# MotorDriver.net
KiCad netlist of a schematic drawn in Altium Designer
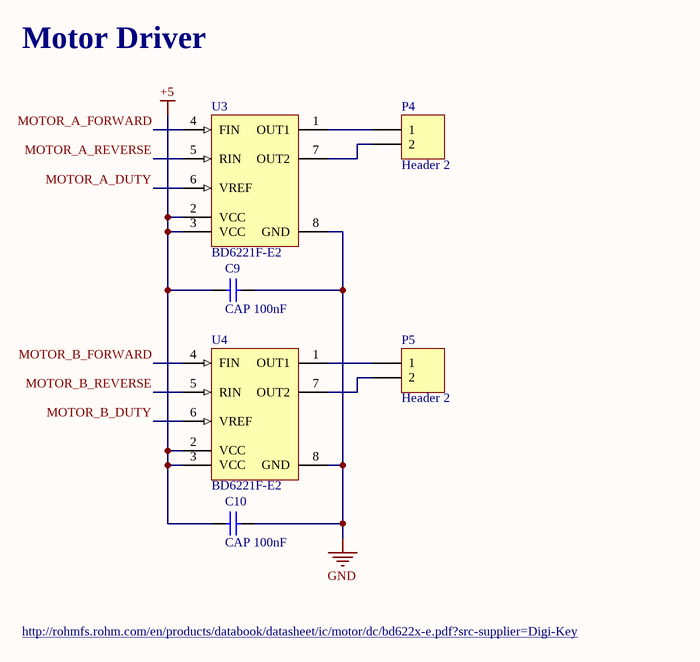
[diagram p0: MotorDriver.SchDoc]

(export (version "E")
  (design (tool "Eeschema 10.0.6"))
  (components
    (comp (ref "C9")
      (value "CAP 100nF")
      (footprint "CAPC0603(1608)100_M")
      (description "CAP 100nF 16V ±5% 0603 (1608 Metric) Thickness 1mm SMD")
      (fields (field (name "TOLERANCE") "Â±5%"))
      (libsource (lib "Altium Content Vault") (part "CAP"))
    )
    (comp (ref "C10")
      (value "CAP 100nF")
      (footprint "CAPC0603(1608)100_M")
      (description "CAP 100nF 16V ±5% 0603 (1608 Metric) Thickness 1mm SMD")
      (fields (field (name "TOLERANCE") "Â±5%"))
      (libsource (lib "Altium Content Vault") (part "CAP"))
    )
    (comp (ref "P4")
      (value "Header 2")
      (footprint "HDR1X2")
      (description "Header, 2-Pin")
      (fields (field (name "PUBLISHER") "Altium Limited"))
      (libsource (lib "Miscellaneous Connectors") (part "Header 2"))
    )
    (comp (ref "P5")
      (value "Header 2")
      (footprint "HDR1X2")
      (description "Header, 2-Pin")
      (fields (field (name "PUBLISHER") "Altium Limited"))
      (libsource (lib "Miscellaneous Connectors") (part "Header 2"))
    )
    (comp (ref "U3")
      (value "BD6221F-E2")
      (footprint "ROHM-SOP-8_V")
      (description "DC Brush Motor Driver, 6 to 18 V, 1 A, -40 to 85 degC, 8-Pin SOP, RoHS, Tape and Reel")
      (fields (field (name "MANUFACTURER") "ROHM Semiconductor"))
      (libsource (lib "Altium Content Vault") (part "ROHM-BD6221F-SOP-8"))
    )
    (comp (ref "U4")
      (value "BD6221F-E2")
      (footprint "ROHM-SOP-8_V")
      (description "DC Brush Motor Driver, 6 to 18 V, 1 A, -40 to 85 degC, 8-Pin SOP, RoHS, Tape and Reel")
      (fields (field (name "MANUFACTURER") "ROHM Semiconductor"))
      (libsource (lib "Altium Content Vault") (part "ROHM-BD6221F-SOP-8"))
    )
  )
  (nets
    (net (code "1") (name "+5") (class "Default")
      (node (ref "C10") (pin "2") (pinfunction "2_2") (pintype "passive"))
      (node (ref "C9") (pin "2") (pinfunction "2_2") (pintype "passive"))
      (node (ref "U3") (pin "2") (pinfunction "VCC_2") (pintype "power_in"))
      (node (ref "U3") (pin "3") (pinfunction "VCC_3") (pintype "power_in"))
      (node (ref "U4") (pin "2") (pinfunction "VCC_2") (pintype "power_in"))
      (node (ref "U4") (pin "3") (pinfunction "VCC_3") (pintype "power_in"))
    )
    (net (code "2") (name "/MOTOR_A_DUTY") (class "Default")
      (node (ref "U3") (pin "6") (pinfunction "VREF_6") (pintype "input"))
    )
    (net (code "3") (name "/MOTOR_A_FORWARD") (class "Default")
      (node (ref "U3") (pin "4") (pinfunction "FIN_4") (pintype "input"))
    )
    (net (code "4") (name "/MOTOR_A_REVERSE") (class "Default")
      (node (ref "U3") (pin "5") (pinfunction "RIN_5") (pintype "input"))
    )
    (net (code "5") (name "/MOTOR_B_DUTY") (class "Default")
      (node (ref "U4") (pin "6") (pinfunction "VREF_6") (pintype "input"))
    )
    (net (code "6") (name "/MOTOR_B_FORWARD") (class "Default")
      (node (ref "U4") (pin "4") (pinfunction "FIN_4") (pintype "input"))
    )
    (net (code "7") (name "/MOTOR_B_REVERSE") (class "Default")
      (node (ref "U4") (pin "5") (pinfunction "RIN_5") (pintype "input"))
    )
    (net (code "8") (name "GND") (class "Default")
      (node (ref "C10") (pin "1") (pinfunction "1_1") (pintype "passive"))
      (node (ref "C9") (pin "1") (pinfunction "1_1") (pintype "passive"))
      (node (ref "U3") (pin "8") (pinfunction "GND_8") (pintype "power_in"))
      (node (ref "U4") (pin "8") (pinfunction "GND_8") (pintype "power_in"))
    )
    (net (code "9") (name "Net-(U3-OUT1)") (class "Default")
      (node (ref "P4") (pin "1") (pinfunction "1_1") (pintype "passive"))
      (node (ref "U3") (pin "1") (pinfunction "OUT1_1") (pintype "tri_state"))
    )
    (net (code "10") (name "Net-(U3-OUT2)") (class "Default")
      (node (ref "P4") (pin "2") (pinfunction "2_2") (pintype "passive"))
      (node (ref "U3") (pin "7") (pinfunction "OUT2_7") (pintype "tri_state"))
    )
    (net (code "11") (name "Net-(U4-OUT1)") (class "Default")
      (node (ref "P5") (pin "1") (pinfunction "1_1") (pintype "passive"))
      (node (ref "U4") (pin "1") (pinfunction "OUT1_1") (pintype "tri_state"))
    )
    (net (code "12") (name "Net-(U4-OUT2)") (class "Default")
      (node (ref "P5") (pin "2") (pinfunction "2_2") (pintype "passive"))
      (node (ref "U4") (pin "7") (pinfunction "OUT2_7") (pintype "tri_state"))
    )
  )
)
